# Keyboard_Mechanical.net
KiCad netlist of a schematic drawn in Altium Designer
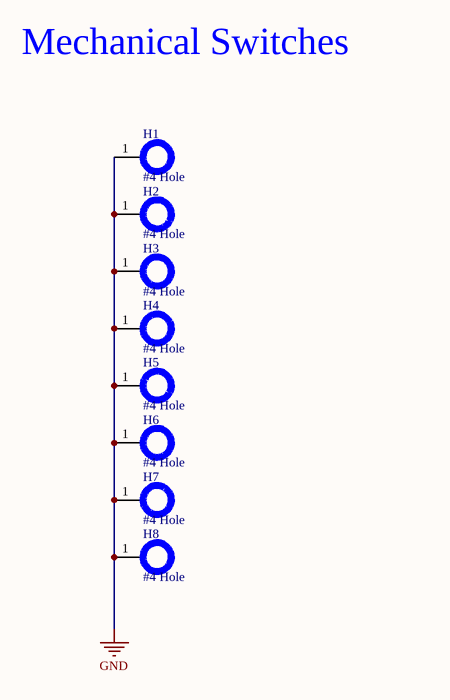
[diagram p0: Keyboard_Mechanical.SchDoc]

(export (version "E")
  (design (tool "Eeschema 10.0.6"))
  (components
    (comp (ref "H1") (value "#4 Hole") (footprint "Hole") (libsource (lib "Keyboard_parts") (part "HOLE_#4")))
    (comp (ref "H2") (value "#4 Hole") (footprint "Hole") (libsource (lib "Keyboard_parts") (part "HOLE_#4")))
    (comp (ref "H3") (value "#4 Hole") (footprint "Hole") (libsource (lib "Keyboard_parts") (part "HOLE_#4")))
    (comp (ref "H4") (value "#4 Hole") (footprint "Hole") (libsource (lib "Keyboard_parts") (part "HOLE_#4")))
    (comp (ref "H5") (value "#4 Hole") (footprint "Hole") (libsource (lib "Keyboard_parts") (part "HOLE_#4")))
    (comp (ref "H6") (value "#4 Hole") (footprint "Hole") (libsource (lib "Keyboard_parts") (part "HOLE_#4")))
    (comp (ref "H7") (value "#4 Hole") (footprint "Hole") (libsource (lib "Keyboard_parts") (part "HOLE_#4")))
    (comp (ref "H8") (value "#4 Hole") (footprint "Hole") (libsource (lib "Keyboard_parts") (part "HOLE_#4")))
  )
  (nets
    (net (code "1") (name "GND") (class "Default")
      (node (ref "H1") (pin "1") (pinfunction "1_1") (pintype "passive"))
      (node (ref "H2") (pin "1") (pinfunction "1_1") (pintype "passive"))
      (node (ref "H3") (pin "1") (pinfunction "1_1") (pintype "passive"))
      (node (ref "H4") (pin "1") (pinfunction "1_1") (pintype "passive"))
      (node (ref "H5") (pin "1") (pinfunction "1_1") (pintype "passive"))
      (node (ref "H6") (pin "1") (pinfunction "1_1") (pintype "passive"))
      (node (ref "H7") (pin "1") (pinfunction "1_1") (pintype "passive"))
      (node (ref "H8") (pin "1") (pinfunction "1_1") (pintype "passive"))
    )
  )
)
